# 10-M2_GPS.net
KiCad netlist of a schematic drawn in Altium Designer
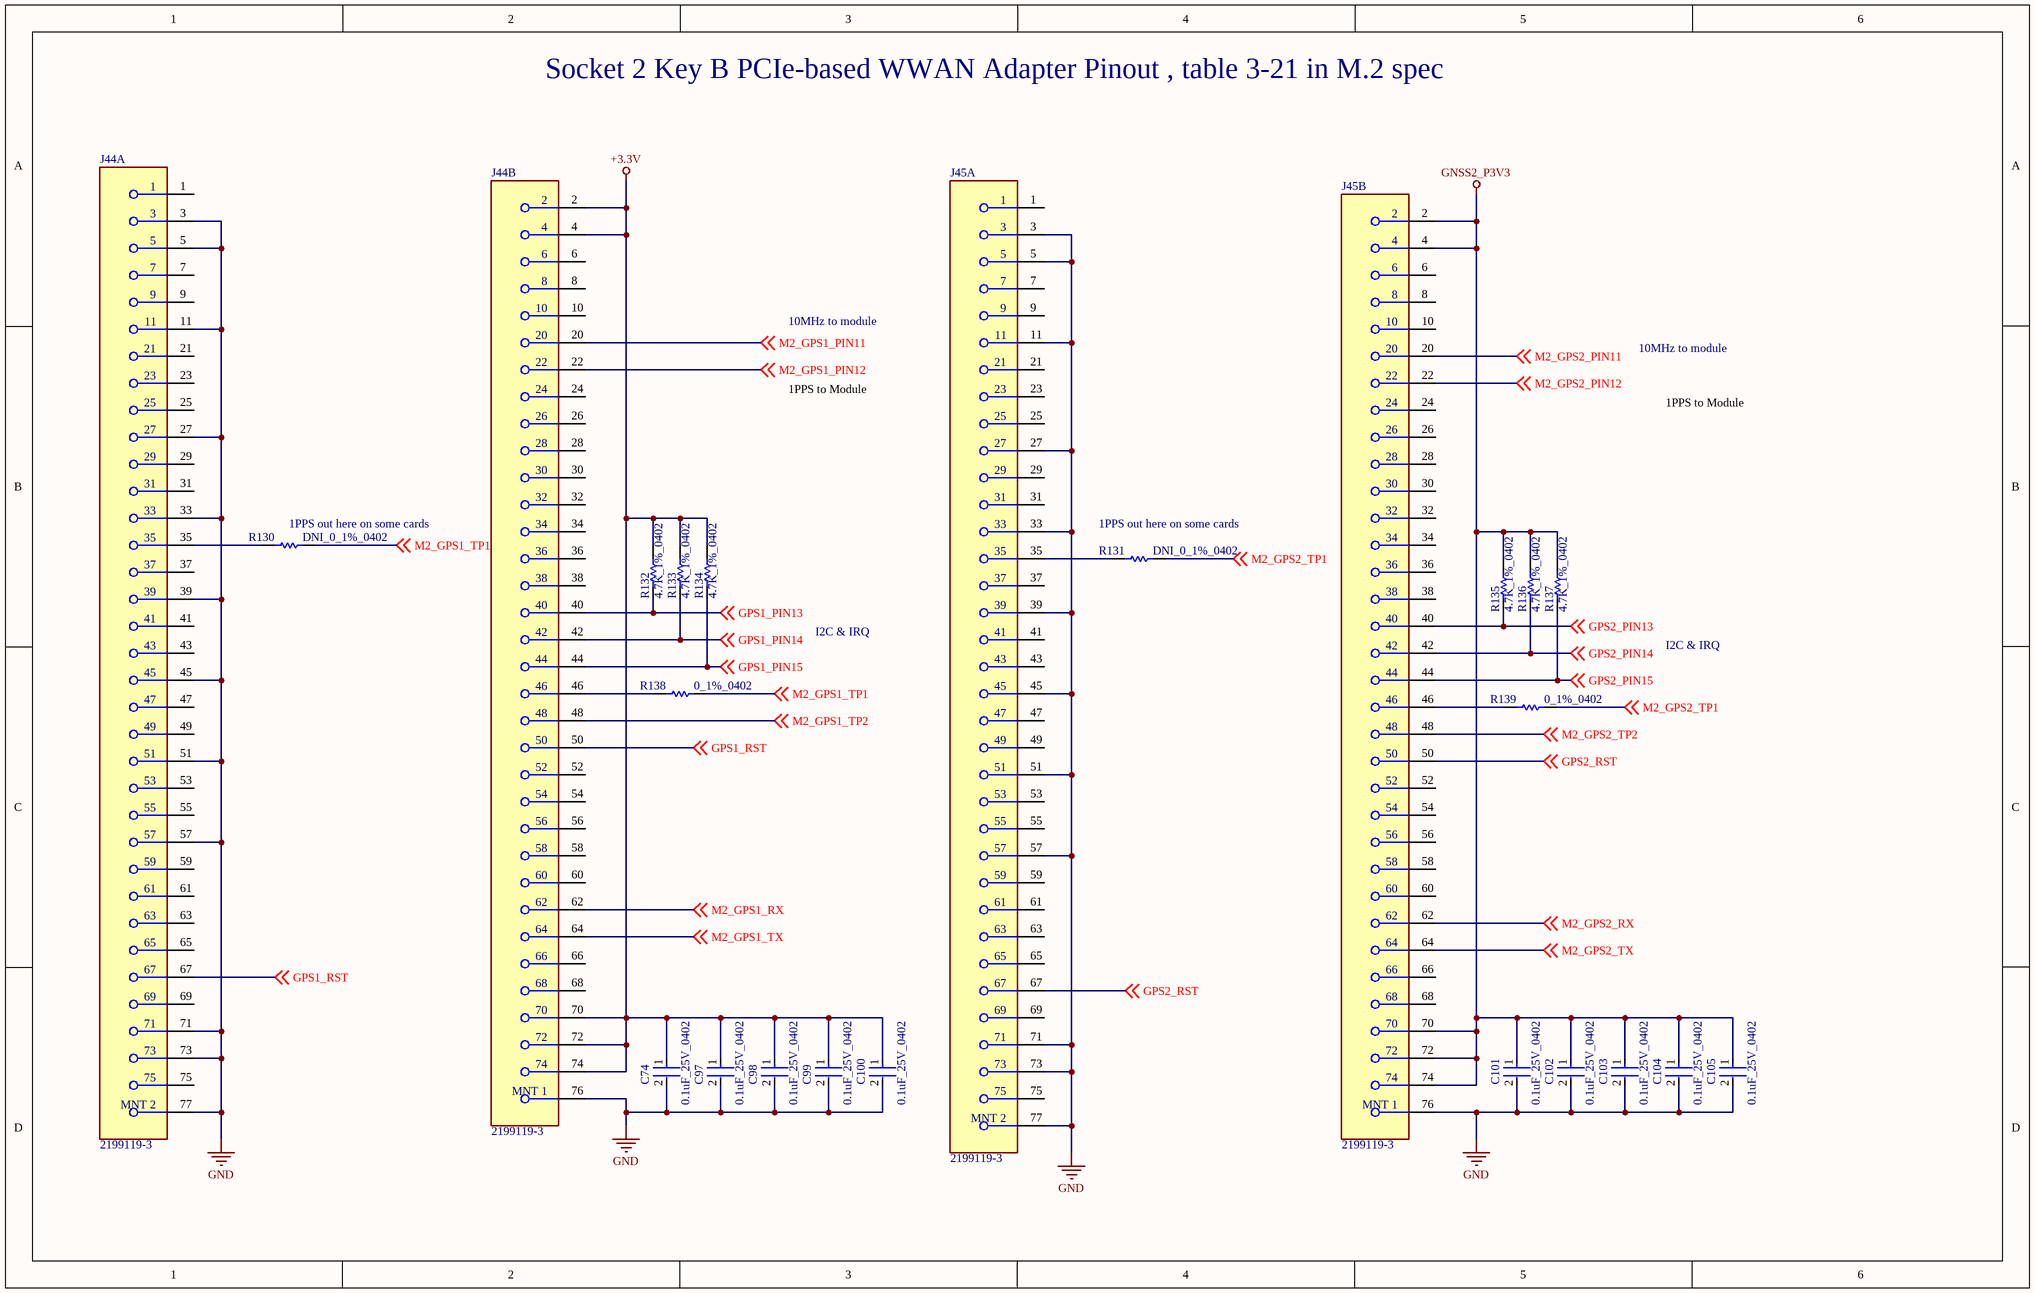
[diagram p0: 10-M2_GPS.SchDoc]

(export (version "E")
  (design (tool "Eeschema 10.0.6"))
  (components
    (comp (ref "C74")
      (value "0.1uF_25V_0402")
      (footprint "FP-0402-L_1_0_1-W_0_5_0_1-IPC_C")
      (description "General Purpose Ceramic Capacitor, 0402, 100nF, 10%, X7R, 15%, 25V")
      (fields (field (name "VOLTAGE") "25V") (field (name "TOLERANCE") "10%"))
      (libsource (lib "Altium Content Vault") (part "b4654b650e69147ec39a6b967a45e02"))
    )
    (comp (ref "C97")
      (value "0.1uF_25V_0402")
      (footprint "FP-0402-L_1_0_1-W_0_5_0_1-IPC_C")
      (description "General Purpose Ceramic Capacitor, 0402, 100nF, 10%, X7R, 15%, 25V")
      (fields (field (name "VOLTAGE") "25V") (field (name "TOLERANCE") "10%"))
      (libsource (lib "Altium Content Vault") (part "b4654b650e69147ec39a6b967a45e02"))
    )
    (comp (ref "C98")
      (value "0.1uF_25V_0402")
      (footprint "FP-0402-L_1_0_1-W_0_5_0_1-IPC_C")
      (description "General Purpose Ceramic Capacitor, 0402, 100nF, 10%, X7R, 15%, 25V")
      (fields (field (name "VOLTAGE") "25V") (field (name "TOLERANCE") "10%"))
      (libsource (lib "Altium Content Vault") (part "b4654b650e69147ec39a6b967a45e02"))
    )
    (comp (ref "C99")
      (value "0.1uF_25V_0402")
      (footprint "FP-0402-L_1_0_1-W_0_5_0_1-IPC_C")
      (description "General Purpose Ceramic Capacitor, 0402, 100nF, 10%, X7R, 15%, 25V")
      (fields (field (name "VOLTAGE") "25V") (field (name "TOLERANCE") "10%"))
      (libsource (lib "Altium Content Vault") (part "b4654b650e69147ec39a6b967a45e02"))
    )
    (comp (ref "C100")
      (value "0.1uF_25V_0402")
      (footprint "FP-0402-L_1_0_1-W_0_5_0_1-IPC_C")
      (description "General Purpose Ceramic Capacitor, 0402, 100nF, 10%, X7R, 15%, 25V")
      (fields (field (name "VOLTAGE") "25V") (field (name "TOLERANCE") "10%"))
      (libsource (lib "Altium Content Vault") (part "b4654b650e69147ec39a6b967a45e02"))
    )
    (comp (ref "C101")
      (value "0.1uF_25V_0402")
      (footprint "FP-0402-L_1_0_1-W_0_5_0_1-IPC_C")
      (description "General Purpose Ceramic Capacitor, 0402, 100nF, 10%, X7R, 15%, 25V")
      (fields (field (name "VOLTAGE") "25V") (field (name "TOLERANCE") "10%"))
      (libsource (lib "Altium Content Vault") (part "b4654b650e69147ec39a6b967a45e02"))
    )
    (comp (ref "C102")
      (value "0.1uF_25V_0402")
      (footprint "FP-0402-L_1_0_1-W_0_5_0_1-IPC_C")
      (description "General Purpose Ceramic Capacitor, 0402, 100nF, 10%, X7R, 15%, 25V")
      (fields (field (name "VOLTAGE") "25V") (field (name "TOLERANCE") "10%"))
      (libsource (lib "Altium Content Vault") (part "b4654b650e69147ec39a6b967a45e02"))
    )
    (comp (ref "C103")
      (value "0.1uF_25V_0402")
      (footprint "FP-0402-L_1_0_1-W_0_5_0_1-IPC_C")
      (description "General Purpose Ceramic Capacitor, 0402, 100nF, 10%, X7R, 15%, 25V")
      (fields (field (name "VOLTAGE") "25V") (field (name "TOLERANCE") "10%"))
      (libsource (lib "Altium Content Vault") (part "b4654b650e69147ec39a6b967a45e02"))
    )
    (comp (ref "C104")
      (value "0.1uF_25V_0402")
      (footprint "FP-0402-L_1_0_1-W_0_5_0_1-IPC_C")
      (description "General Purpose Ceramic Capacitor, 0402, 100nF, 10%, X7R, 15%, 25V")
      (fields (field (name "VOLTAGE") "25V") (field (name "TOLERANCE") "10%"))
      (libsource (lib "Altium Content Vault") (part "b4654b650e69147ec39a6b967a45e02"))
    )
    (comp (ref "C105")
      (value "0.1uF_25V_0402")
      (footprint "FP-0402-L_1_0_1-W_0_5_0_1-IPC_C")
      (description "General Purpose Ceramic Capacitor, 0402, 100nF, 10%, X7R, 15%, 25V")
      (fields (field (name "VOLTAGE") "25V") (field (name "TOLERANCE") "10%"))
      (libsource (lib "Altium Content Vault") (part "b4654b650e69147ec39a6b967a45e02"))
    )
    (comp (ref "J44")
      (value "2199119-3")
      (footprint "FP-2199119-3-MFG")
      (description "CONN M.2 FEMALE 67POS 0.020 GOLD")
      (libsource (lib "Altium Content Vault") (part "a14843ccfa78e5d0b739856168502fb"))
    )
    (comp (ref "J45")
      (value "2199119-3")
      (footprint "FP-2199119-3-MFG")
      (description "CONN M.2 FEMALE 67POS 0.020 GOLD")
      (libsource (lib "Altium Content Vault") (part "a14843ccfa78e5d0b739856168502fb"))
    )
    (comp (ref "R130")
      (value "DNI_0_1%_0402")
      (footprint "RESC1005X40X25LL05T05")
      (description "Chip Resistor, 0 Ohm, 0.1 W, -55 to 155 degC, 0402 (1005 Metric), RoHS, Tape and Reel")
      (fields (field (name "MANUFACTURER") "Panasonic") (field (name "TOLERANCE") "5%"))
      (libsource (lib "Altium Content Vault") (part "RES-2"))
    )
    (comp (ref "R131")
      (value "DNI_0_1%_0402")
      (footprint "RESC1005X40X25LL05T05")
      (description "Chip Resistor, 0 Ohm, 0.1 W, -55 to 155 degC, 0402 (1005 Metric), RoHS, Tape and Reel")
      (fields (field (name "MANUFACTURER") "Panasonic") (field (name "TOLERANCE") "5%"))
      (libsource (lib "Altium Content Vault") (part "RES-2"))
    )
    (comp (ref "R132")
      (value "4.7K_1%_0402")
      (footprint "RESC1005X40X25NL10T10")
      (fields (field (name "MANUFACTURER") "Bourns") (field (name "PART NUMBER") "CR0402-FX-4701GLF"))
      (libsource (lib "Altium Content Vault") (part "RES"))
    )
    (comp (ref "R133")
      (value "4.7K_1%_0402")
      (footprint "RESC1005X40X25NL10T10")
      (fields (field (name "MANUFACTURER") "Bourns") (field (name "PART NUMBER") "CR0402-FX-4701GLF"))
      (libsource (lib "Altium Content Vault") (part "RES"))
    )
    (comp (ref "R134")
      (value "4.7K_1%_0402")
      (footprint "RESC1005X40X25NL10T10")
      (fields (field (name "MANUFACTURER") "Bourns") (field (name "PART NUMBER") "CR0402-FX-4701GLF"))
      (libsource (lib "Altium Content Vault") (part "RES"))
    )
    (comp (ref "R135")
      (value "4.7K_1%_0402")
      (footprint "RESC1005X40X25NL10T10")
      (fields (field (name "MANUFACTURER") "Bourns") (field (name "PART NUMBER") "CR0402-FX-4701GLF"))
      (libsource (lib "Altium Content Vault") (part "RES"))
    )
    (comp (ref "R136")
      (value "4.7K_1%_0402")
      (footprint "RESC1005X40X25NL10T10")
      (fields (field (name "MANUFACTURER") "Bourns") (field (name "PART NUMBER") "CR0402-FX-4701GLF"))
      (libsource (lib "Altium Content Vault") (part "RES"))
    )
    (comp (ref "R137")
      (value "4.7K_1%_0402")
      (footprint "RESC1005X40X25NL10T10")
      (fields (field (name "MANUFACTURER") "Bourns") (field (name "PART NUMBER") "CR0402-FX-4701GLF"))
      (libsource (lib "Altium Content Vault") (part "RES"))
    )
    (comp (ref "R138")
      (value "0_1%_0402")
      (footprint "RESC1005X40X25LL05T05")
      (description "Chip Resistor, 0 Ohm, 0.1 W, -55 to 155 degC, 0402 (1005 Metric), RoHS, Tape and Reel")
      (fields (field (name "MANUFACTURER") "Panasonic") (field (name "TOLERANCE") "5%"))
      (libsource (lib "Altium Content Vault") (part "RES-2"))
    )
    (comp (ref "R139")
      (value "0_1%_0402")
      (footprint "RESC1005X40X25LL05T05")
      (description "Chip Resistor, 0 Ohm, 0.1 W, -55 to 155 degC, 0402 (1005 Metric), RoHS, Tape and Reel")
      (fields (field (name "MANUFACTURER") "Panasonic") (field (name "TOLERANCE") "5%"))
      (libsource (lib "Altium Content Vault") (part "RES-2"))
    )
  )
  (nets
    (net (code "1") (name "+3.3V") (class "Default")
      (node (ref "C100") (pin "1") (pinfunction "1_1") (pintype "passive"))
      (node (ref "C74") (pin "1") (pinfunction "1_1") (pintype "passive"))
      (node (ref "C97") (pin "1") (pinfunction "1_1") (pintype "passive"))
      (node (ref "C98") (pin "1") (pinfunction "1_1") (pintype "passive"))
      (node (ref "C99") (pin "1") (pinfunction "1_1") (pintype "passive"))
      (node (ref "J44") (pin "2") (pinfunction "2_2") (pintype "passive"))
      (node (ref "J44") (pin "4") (pinfunction "4_4") (pintype "passive"))
      (node (ref "J44") (pin "70") (pinfunction "70_70") (pintype "passive"))
      (node (ref "J44") (pin "72") (pinfunction "72_72") (pintype "passive"))
      (node (ref "J44") (pin "74") (pinfunction "74_74") (pintype "passive"))
      (node (ref "R132") (pin "2") (pinfunction "2_2") (pintype "passive"))
      (node (ref "R133") (pin "2") (pinfunction "2_2") (pintype "passive"))
      (node (ref "R134") (pin "2") (pinfunction "2_2") (pintype "passive"))
    )
    (net (code "2") (name "GND") (class "Default")
      (node (ref "C100") (pin "2") (pinfunction "2_2") (pintype "passive"))
      (node (ref "C101") (pin "2") (pinfunction "2_2") (pintype "passive"))
      (node (ref "C102") (pin "2") (pinfunction "2_2") (pintype "passive"))
      (node (ref "C103") (pin "2") (pinfunction "2_2") (pintype "passive"))
      (node (ref "C104") (pin "2") (pinfunction "2_2") (pintype "passive"))
      (node (ref "C105") (pin "2") (pinfunction "2_2") (pintype "passive"))
      (node (ref "C74") (pin "2") (pinfunction "2_2") (pintype "passive"))
      (node (ref "C97") (pin "2") (pinfunction "2_2") (pintype "passive"))
      (node (ref "C98") (pin "2") (pinfunction "2_2") (pintype "passive"))
      (node (ref "C99") (pin "2") (pinfunction "2_2") (pintype "passive"))
      (node (ref "J44") (pin "11") (pinfunction "11_11") (pintype "passive"))
      (node (ref "J44") (pin "27") (pinfunction "27_27") (pintype "passive"))
      (node (ref "J44") (pin "3") (pinfunction "3_3") (pintype "passive"))
      (node (ref "J44") (pin "33") (pinfunction "33_33") (pintype "passive"))
      (node (ref "J44") (pin "39") (pinfunction "39_39") (pintype "passive"))
      (node (ref "J44") (pin "45") (pinfunction "45_45") (pintype "passive"))
      (node (ref "J44") (pin "5") (pinfunction "5_5") (pintype "passive"))
      (node (ref "J44") (pin "51") (pinfunction "51_51") (pintype "passive"))
      (node (ref "J44") (pin "57") (pinfunction "57_57") (pintype "passive"))
      (node (ref "J44") (pin "71") (pinfunction "71_71") (pintype "passive"))
      (node (ref "J44") (pin "73") (pinfunction "73_73") (pintype "passive"))
      (node (ref "J44") (pin "76") (pinfunction "MNT_1_76") (pintype "passive"))
      (node (ref "J44") (pin "77") (pinfunction "MNT_2_77") (pintype "passive"))
      (node (ref "J45") (pin "11") (pinfunction "11_11") (pintype "passive"))
      (node (ref "J45") (pin "27") (pinfunction "27_27") (pintype "passive"))
      (node (ref "J45") (pin "3") (pinfunction "3_3") (pintype "passive"))
      (node (ref "J45") (pin "33") (pinfunction "33_33") (pintype "passive"))
      (node (ref "J45") (pin "39") (pinfunction "39_39") (pintype "passive"))
      (node (ref "J45") (pin "45") (pinfunction "45_45") (pintype "passive"))
      (node (ref "J45") (pin "5") (pinfunction "5_5") (pintype "passive"))
      (node (ref "J45") (pin "51") (pinfunction "51_51") (pintype "passive"))
      (node (ref "J45") (pin "57") (pinfunction "57_57") (pintype "passive"))
      (node (ref "J45") (pin "71") (pinfunction "71_71") (pintype "passive"))
      (node (ref "J45") (pin "73") (pinfunction "73_73") (pintype "passive"))
      (node (ref "J45") (pin "76") (pinfunction "MNT_1_76") (pintype "passive"))
      (node (ref "J45") (pin "77") (pinfunction "MNT_2_77") (pintype "passive"))
    )
    (net (code "3") (name "GNSS2_P3V3") (class "Default")
      (node (ref "C101") (pin "1") (pinfunction "1_1") (pintype "passive"))
      (node (ref "C102") (pin "1") (pinfunction "1_1") (pintype "passive"))
      (node (ref "C103") (pin "1") (pinfunction "1_1") (pintype "passive"))
      (node (ref "C104") (pin "1") (pinfunction "1_1") (pintype "passive"))
      (node (ref "C105") (pin "1") (pinfunction "1_1") (pintype "passive"))
      (node (ref "J45") (pin "2") (pinfunction "2_2") (pintype "passive"))
      (node (ref "J45") (pin "4") (pinfunction "4_4") (pintype "passive"))
      (node (ref "J45") (pin "70") (pinfunction "70_70") (pintype "passive"))
      (node (ref "J45") (pin "72") (pinfunction "72_72") (pintype "passive"))
      (node (ref "J45") (pin "74") (pinfunction "74_74") (pintype "passive"))
      (node (ref "R135") (pin "2") (pinfunction "2_2") (pintype "passive"))
      (node (ref "R136") (pin "2") (pinfunction "2_2") (pintype "passive"))
      (node (ref "R137") (pin "2") (pinfunction "2_2") (pintype "passive"))
    )
    (net (code "4") (name "GPS1_PIN13") (class "Default")
      (node (ref "J44") (pin "40") (pinfunction "40_40") (pintype "passive"))
      (node (ref "R132") (pin "1") (pinfunction "1_1") (pintype "passive"))
    )
    (net (code "5") (name "GPS1_PIN14") (class "Default")
      (node (ref "J44") (pin "42") (pinfunction "42_42") (pintype "passive"))
      (node (ref "R133") (pin "1") (pinfunction "1_1") (pintype "passive"))
    )
    (net (code "6") (name "GPS1_PIN15") (class "Default")
      (node (ref "J44") (pin "44") (pinfunction "44_44") (pintype "passive"))
      (node (ref "R134") (pin "1") (pinfunction "1_1") (pintype "passive"))
    )
    (net (code "7") (name "GPS1_RST") (class "Default")
      (node (ref "J44") (pin "50") (pinfunction "50_50") (pintype "passive"))
      (node (ref "J44") (pin "67") (pinfunction "67_67") (pintype "passive"))
    )
    (net (code "8") (name "GPS2_PIN13") (class "Default")
      (node (ref "J45") (pin "40") (pinfunction "40_40") (pintype "passive"))
      (node (ref "R135") (pin "1") (pinfunction "1_1") (pintype "passive"))
    )
    (net (code "9") (name "GPS2_PIN14") (class "Default")
      (node (ref "J45") (pin "42") (pinfunction "42_42") (pintype "passive"))
      (node (ref "R136") (pin "1") (pinfunction "1_1") (pintype "passive"))
    )
    (net (code "10") (name "GPS2_PIN15") (class "Default")
      (node (ref "J45") (pin "44") (pinfunction "44_44") (pintype "passive"))
      (node (ref "R137") (pin "1") (pinfunction "1_1") (pintype "passive"))
    )
    (net (code "11") (name "GPS2_RST") (class "Default")
      (node (ref "J45") (pin "50") (pinfunction "50_50") (pintype "passive"))
      (node (ref "J45") (pin "67") (pinfunction "67_67") (pintype "passive"))
    )
    (net (code "12") (name "M2_GPS1_PIN11") (class "Default")
      (node (ref "J44") (pin "20") (pinfunction "20_20") (pintype "passive"))
    )
    (net (code "13") (name "M2_GPS1_PIN12") (class "Default")
      (node (ref "J44") (pin "22") (pinfunction "22_22") (pintype "passive"))
    )
    (net (code "14") (name "M2_GPS1_RX") (class "Default")
      (node (ref "J44") (pin "62") (pinfunction "62_62") (pintype "passive"))
    )
    (net (code "15") (name "M2_GPS1_TP1") (class "Default")
      (node (ref "R130") (pin "2") (pinfunction "2_2") (pintype "passive"))
      (node (ref "R138") (pin "2") (pinfunction "2_2") (pintype "passive"))
    )
    (net (code "16") (name "M2_GPS1_TP2") (class "Default")
      (node (ref "J44") (pin "48") (pinfunction "48_48") (pintype "passive"))
    )
    (net (code "17") (name "M2_GPS1_TX") (class "Default")
      (node (ref "J44") (pin "64") (pinfunction "64_64") (pintype "passive"))
    )
    (net (code "18") (name "M2_GPS2_PIN11") (class "Default")
      (node (ref "J45") (pin "20") (pinfunction "20_20") (pintype "passive"))
    )
    (net (code "19") (name "M2_GPS2_PIN12") (class "Default")
      (node (ref "J45") (pin "22") (pinfunction "22_22") (pintype "passive"))
    )
    (net (code "20") (name "M2_GPS2_RX") (class "Default")
      (node (ref "J45") (pin "62") (pinfunction "62_62") (pintype "passive"))
    )
    (net (code "21") (name "M2_GPS2_TP1") (class "Default")
      (node (ref "R131") (pin "2") (pinfunction "2_2") (pintype "passive"))
      (node (ref "R139") (pin "2") (pinfunction "2_2") (pintype "passive"))
    )
    (net (code "22") (name "M2_GPS2_TP2") (class "Default")
      (node (ref "J45") (pin "48") (pinfunction "48_48") (pintype "passive"))
    )
    (net (code "23") (name "M2_GPS2_TX") (class "Default")
      (node (ref "J45") (pin "64") (pinfunction "64_64") (pintype "passive"))
    )
    (net (code "24") (name "Net-(J44-Pad35)") (class "Default")
      (node (ref "J44") (pin "35") (pinfunction "35_35") (pintype "passive"))
      (node (ref "R130") (pin "1") (pinfunction "1_1") (pintype "passive"))
    )
    (net (code "25") (name "Net-(J44-Pad46)") (class "Default")
      (node (ref "J44") (pin "46") (pinfunction "46_46") (pintype "passive"))
      (node (ref "R138") (pin "1") (pinfunction "1_1") (pintype "passive"))
    )
    (net (code "26") (name "Net-(J45-Pad35)") (class "Default")
      (node (ref "J45") (pin "35") (pinfunction "35_35") (pintype "passive"))
      (node (ref "R131") (pin "1") (pinfunction "1_1") (pintype "passive"))
    )
    (net (code "27") (name "Net-(J45-Pad46)") (class "Default")
      (node (ref "J45") (pin "46") (pinfunction "46_46") (pintype "passive"))
      (node (ref "R139") (pin "1") (pinfunction "1_1") (pintype "passive"))
    )
    (net (code "28") (name "unconnected-(J44-Pad1)") (class "Default")
      (node (ref "J44") (pin "1") (pinfunction "1_1") (pintype "passive"))
    )
    (net (code "29") (name "unconnected-(J44-Pad6)") (class "Default")
      (node (ref "J44") (pin "6") (pinfunction "6_6") (pintype "passive"))
    )
    (net (code "30") (name "unconnected-(J44-Pad7)") (class "Default")
      (node (ref "J44") (pin "7") (pinfunction "7_7") (pintype "passive"))
    )
    (net (code "31") (name "unconnected-(J44-Pad8)") (class "Default")
      (node (ref "J44") (pin "8") (pinfunction "8_8") (pintype "passive"))
    )
    (net (code "32") (name "unconnected-(J44-Pad9)") (class "Default")
      (node (ref "J44") (pin "9") (pinfunction "9_9") (pintype "passive"))
    )
    (net (code "33") (name "unconnected-(J44-Pad10)") (class "Default")
      (node (ref "J44") (pin "10") (pinfunction "10_10") (pintype "passive"))
    )
    (net (code "34") (name "unconnected-(J44-Pad21)") (class "Default")
      (node (ref "J44") (pin "21") (pinfunction "21_21") (pintype "passive"))
    )
    (net (code "35") (name "unconnected-(J44-Pad23)") (class "Default")
      (node (ref "J44") (pin "23") (pinfunction "23_23") (pintype "passive"))
    )
    (net (code "36") (name "unconnected-(J44-Pad24)") (class "Default")
      (node (ref "J44") (pin "24") (pinfunction "24_24") (pintype "passive"))
    )
    (net (code "37") (name "unconnected-(J44-Pad25)") (class "Default")
      (node (ref "J44") (pin "25") (pinfunction "25_25") (pintype "passive"))
    )
    (net (code "38") (name "unconnected-(J44-Pad26)") (class "Default")
      (node (ref "J44") (pin "26") (pinfunction "26_26") (pintype "passive"))
    )
    (net (code "39") (name "unconnected-(J44-Pad28)") (class "Default")
      (node (ref "J44") (pin "28") (pinfunction "28_28") (pintype "passive"))
    )
    (net (code "40") (name "unconnected-(J44-Pad29)") (class "Default")
      (node (ref "J44") (pin "29") (pinfunction "29_29") (pintype "passive"))
    )
    (net (code "41") (name "unconnected-(J44-Pad30)") (class "Default")
      (node (ref "J44") (pin "30") (pinfunction "30_30") (pintype "passive"))
    )
    (net (code "42") (name "unconnected-(J44-Pad31)") (class "Default")
      (node (ref "J44") (pin "31") (pinfunction "31_31") (pintype "passive"))
    )
    (net (code "43") (name "unconnected-(J44-Pad32)") (class "Default")
      (node (ref "J44") (pin "32") (pinfunction "32_32") (pintype "passive"))
    )
    (net (code "44") (name "unconnected-(J44-Pad34)") (class "Default")
      (node (ref "J44") (pin "34") (pinfunction "34_34") (pintype "passive"))
    )
    (net (code "45") (name "unconnected-(J44-Pad36)") (class "Default")
      (node (ref "J44") (pin "36") (pinfunction "36_36") (pintype "passive"))
    )
    (net (code "46") (name "unconnected-(J44-Pad37)") (class "Default")
      (node (ref "J44") (pin "37") (pinfunction "37_37") (pintype "passive"))
    )
    (net (code "47") (name "unconnected-(J44-Pad38)") (class "Default")
      (node (ref "J44") (pin "38") (pinfunction "38_38") (pintype "passive"))
    )
    (net (code "48") (name "unconnected-(J44-Pad41)") (class "Default")
      (node (ref "J44") (pin "41") (pinfunction "41_41") (pintype "passive"))
    )
    (net (code "49") (name "unconnected-(J44-Pad43)") (class "Default")
      (node (ref "J44") (pin "43") (pinfunction "43_43") (pintype "passive"))
    )
    (net (code "50") (name "unconnected-(J44-Pad47)") (class "Default")
      (node (ref "J44") (pin "47") (pinfunction "47_47") (pintype "passive"))
    )
    (net (code "51") (name "unconnected-(J44-Pad49)") (class "Default")
      (node (ref "J44") (pin "49") (pinfunction "49_49") (pintype "passive"))
    )
    (net (code "52") (name "unconnected-(J44-Pad52)") (class "Default")
      (node (ref "J44") (pin "52") (pinfunction "52_52") (pintype "passive"))
    )
    (net (code "53") (name "unconnected-(J44-Pad53)") (class "Default")
      (node (ref "J44") (pin "53") (pinfunction "53_53") (pintype "passive"))
    )
    (net (code "54") (name "unconnected-(J44-Pad54)") (class "Default")
      (node (ref "J44") (pin "54") (pinfunction "54_54") (pintype "passive"))
    )
    (net (code "55") (name "unconnected-(J44-Pad55)") (class "Default")
      (node (ref "J44") (pin "55") (pinfunction "55_55") (pintype "passive"))
    )
    (net (code "56") (name "unconnected-(J44-Pad56)") (class "Default")
      (node (ref "J44") (pin "56") (pinfunction "56_56") (pintype "passive"))
    )
    (net (code "57") (name "unconnected-(J44-Pad58)") (class "Default")
      (node (ref "J44") (pin "58") (pinfunction "58_58") (pintype "passive"))
    )
    (net (code "58") (name "unconnected-(J44-Pad59)") (class "Default")
      (node (ref "J44") (pin "59") (pinfunction "59_59") (pintype "passive"))
    )
    (net (code "59") (name "unconnected-(J44-Pad60)") (class "Default")
      (node (ref "J44") (pin "60") (pinfunction "60_60") (pintype "passive"))
    )
    (net (code "60") (name "unconnected-(J44-Pad61)") (class "Default")
      (node (ref "J44") (pin "61") (pinfunction "61_61") (pintype "passive"))
    )
    (net (code "61") (name "unconnected-(J44-Pad63)") (class "Default")
      (node (ref "J44") (pin "63") (pinfunction "63_63") (pintype "passive"))
    )
    (net (code "62") (name "unconnected-(J44-Pad65)") (class "Default")
      (node (ref "J44") (pin "65") (pinfunction "65_65") (pintype "passive"))
    )
    (net (code "63") (name "unconnected-(J44-Pad66)") (class "Default")
      (node (ref "J44") (pin "66") (pinfunction "66_66") (pintype "passive"))
    )
    (net (code "64") (name "unconnected-(J44-Pad68)") (class "Default")
      (node (ref "J44") (pin "68") (pinfunction "68_68") (pintype "passive"))
    )
    (net (code "65") (name "unconnected-(J44-Pad69)") (class "Default")
      (node (ref "J44") (pin "69") (pinfunction "69_69") (pintype "passive"))
    )
    (net (code "66") (name "unconnected-(J44-Pad75)") (class "Default")
      (node (ref "J44") (pin "75") (pinfunction "75_75") (pintype "passive"))
    )
    (net (code "67") (name "unconnected-(J45-Pad1)") (class "Default")
      (node (ref "J45") (pin "1") (pinfunction "1_1") (pintype "passive"))
    )
    (net (code "68") (name "unconnected-(J45-Pad6)") (class "Default")
      (node (ref "J45") (pin "6") (pinfunction "6_6") (pintype "passive"))
    )
    (net (code "69") (name "unconnected-(J45-Pad7)") (class "Default")
      (node (ref "J45") (pin "7") (pinfunction "7_7") (pintype "passive"))
    )
    (net (code "70") (name "unconnected-(J45-Pad8)") (class "Default")
      (node (ref "J45") (pin "8") (pinfunction "8_8") (pintype "passive"))
    )
    (net (code "71") (name "unconnected-(J45-Pad9)") (class "Default")
      (node (ref "J45") (pin "9") (pinfunction "9_9") (pintype "passive"))
    )
    (net (code "72") (name "unconnected-(J45-Pad10)") (class "Default")
      (node (ref "J45") (pin "10") (pinfunction "10_10") (pintype "passive"))
    )
    (net (code "73") (name "unconnected-(J45-Pad21)") (class "Default")
      (node (ref "J45") (pin "21") (pinfunction "21_21") (pintype "passive"))
    )
    (net (code "74") (name "unconnected-(J45-Pad23)") (class "Default")
      (node (ref "J45") (pin "23") (pinfunction "23_23") (pintype "passive"))
    )
    (net (code "75") (name "unconnected-(J45-Pad24)") (class "Default")
      (node (ref "J45") (pin "24") (pinfunction "24_24") (pintype "passive"))
    )
    (net (code "76") (name "unconnected-(J45-Pad25)") (class "Default")
      (node (ref "J45") (pin "25") (pinfunction "25_25") (pintype "passive"))
    )
    (net (code "77") (name "unconnected-(J45-Pad26)") (class "Default")
      (node (ref "J45") (pin "26") (pinfunction "26_26") (pintype "passive"))
    )
    (net (code "78") (name "unconnected-(J45-Pad28)") (class "Default")
      (node (ref "J45") (pin "28") (pinfunction "28_28") (pintype "passive"))
    )
    (net (code "79") (name "unconnected-(J45-Pad29)") (class "Default")
      (node (ref "J45") (pin "29") (pinfunction "29_29") (pintype "passive"))
    )
    (net (code "80") (name "unconnected-(J45-Pad30)") (class "Default")
      (node (ref "J45") (pin "30") (pinfunction "30_30") (pintype "passive"))
    )
    (net (code "81") (name "unconnected-(J45-Pad31)") (class "Default")
      (node (ref "J45") (pin "31") (pinfunction "31_31") (pintype "passive"))
    )
    (net (code "82") (name "unconnected-(J45-Pad32)") (class "Default")
      (node (ref "J45") (pin "32") (pinfunction "32_32") (pintype "passive"))
    )
    (net (code "83") (name "unconnected-(J45-Pad34)") (class "Default")
      (node (ref "J45") (pin "34") (pinfunction "34_34") (pintype "passive"))
    )
    (net (code "84") (name "unconnected-(J45-Pad36)") (class "Default")
      (node (ref "J45") (pin "36") (pinfunction "36_36") (pintype "passive"))
    )
    (net (code "85") (name "unconnected-(J45-Pad37)") (class "Default")
      (node (ref "J45") (pin "37") (pinfunction "37_37") (pintype "passive"))
    )
    (net (code "86") (name "unconnected-(J45-Pad38)") (class "Default")
      (node (ref "J45") (pin "38") (pinfunction "38_38") (pintype "passive"))
    )
    (net (code "87") (name "unconnected-(J45-Pad41)") (class "Default")
      (node (ref "J45") (pin "41") (pinfunction "41_41") (pintype "passive"))
    )
    (net (code "88") (name "unconnected-(J45-Pad43)") (class "Default")
      (node (ref "J45") (pin "43") (pinfunction "43_43") (pintype "passive"))
    )
    (net (code "89") (name "unconnected-(J45-Pad47)") (class "Default")
      (node (ref "J45") (pin "47") (pinfunction "47_47") (pintype "passive"))
    )
    (net (code "90") (name "unconnected-(J45-Pad49)") (class "Default")
      (node (ref "J45") (pin "49") (pinfunction "49_49") (pintype "passive"))
    )
    (net (code "91") (name "unconnected-(J45-Pad52)") (class "Default")
      (node (ref "J45") (pin "52") (pinfunction "52_52") (pintype "passive"))
    )
    (net (code "92") (name "unconnected-(J45-Pad53)") (class "Default")
      (node (ref "J45") (pin "53") (pinfunction "53_53") (pintype "passive"))
    )
    (net (code "93") (name "unconnected-(J45-Pad54)") (class "Default")
      (node (ref "J45") (pin "54") (pinfunction "54_54") (pintype "passive"))
    )
    (net (code "94") (name "unconnected-(J45-Pad55)") (class "Default")
      (node (ref "J45") (pin "55") (pinfunction "55_55") (pintype "passive"))
    )
    (net (code "95") (name "unconnected-(J45-Pad56)") (class "Default")
      (node (ref "J45") (pin "56") (pinfunction "56_56") (pintype "passive"))
    )
    (net (code "96") (name "unconnected-(J45-Pad58)") (class "Default")
      (node (ref "J45") (pin "58") (pinfunction "58_58") (pintype "passive"))
    )
    (net (code "97") (name "unconnected-(J45-Pad59)") (class "Default")
      (node (ref "J45") (pin "59") (pinfunction "59_59") (pintype "passive"))
    )
    (net (code "98") (name "unconnected-(J45-Pad60)") (class "Default")
      (node (ref "J45") (pin "60") (pinfunction "60_60") (pintype "passive"))
    )
    (net (code "99") (name "unconnected-(J45-Pad61)") (class "Default")
      (node (ref "J45") (pin "61") (pinfunction "61_61") (pintype "passive"))
    )
    (net (code "100") (name "unconnected-(J45-Pad63)") (class "Default")
      (node (ref "J45") (pin "63") (pinfunction "63_63") (pintype "passive"))
    )
    (net (code "101") (name "unconnected-(J45-Pad65)") (class "Default")
      (node (ref "J45") (pin "65") (pinfunction "65_65") (pintype "passive"))
    )
    (net (code "102") (name "unconnected-(J45-Pad66)") (class "Default")
      (node (ref "J45") (pin "66") (pinfunction "66_66") (pintype "passive"))
    )
    (net (code "103") (name "unconnected-(J45-Pad68)") (class "Default")
      (node (ref "J45") (pin "68") (pinfunction "68_68") (pintype "passive"))
    )
    (net (code "104") (name "unconnected-(J45-Pad69)") (class "Default")
      (node (ref "J45") (pin "69") (pinfunction "69_69") (pintype "passive"))
    )
    (net (code "105") (name "unconnected-(J45-Pad75)") (class "Default")
      (node (ref "J45") (pin "75") (pinfunction "75_75") (pintype "passive"))
    )
  )
)
